# uc_board2.net
KiCad netlist of a schematic drawn in EAGLE
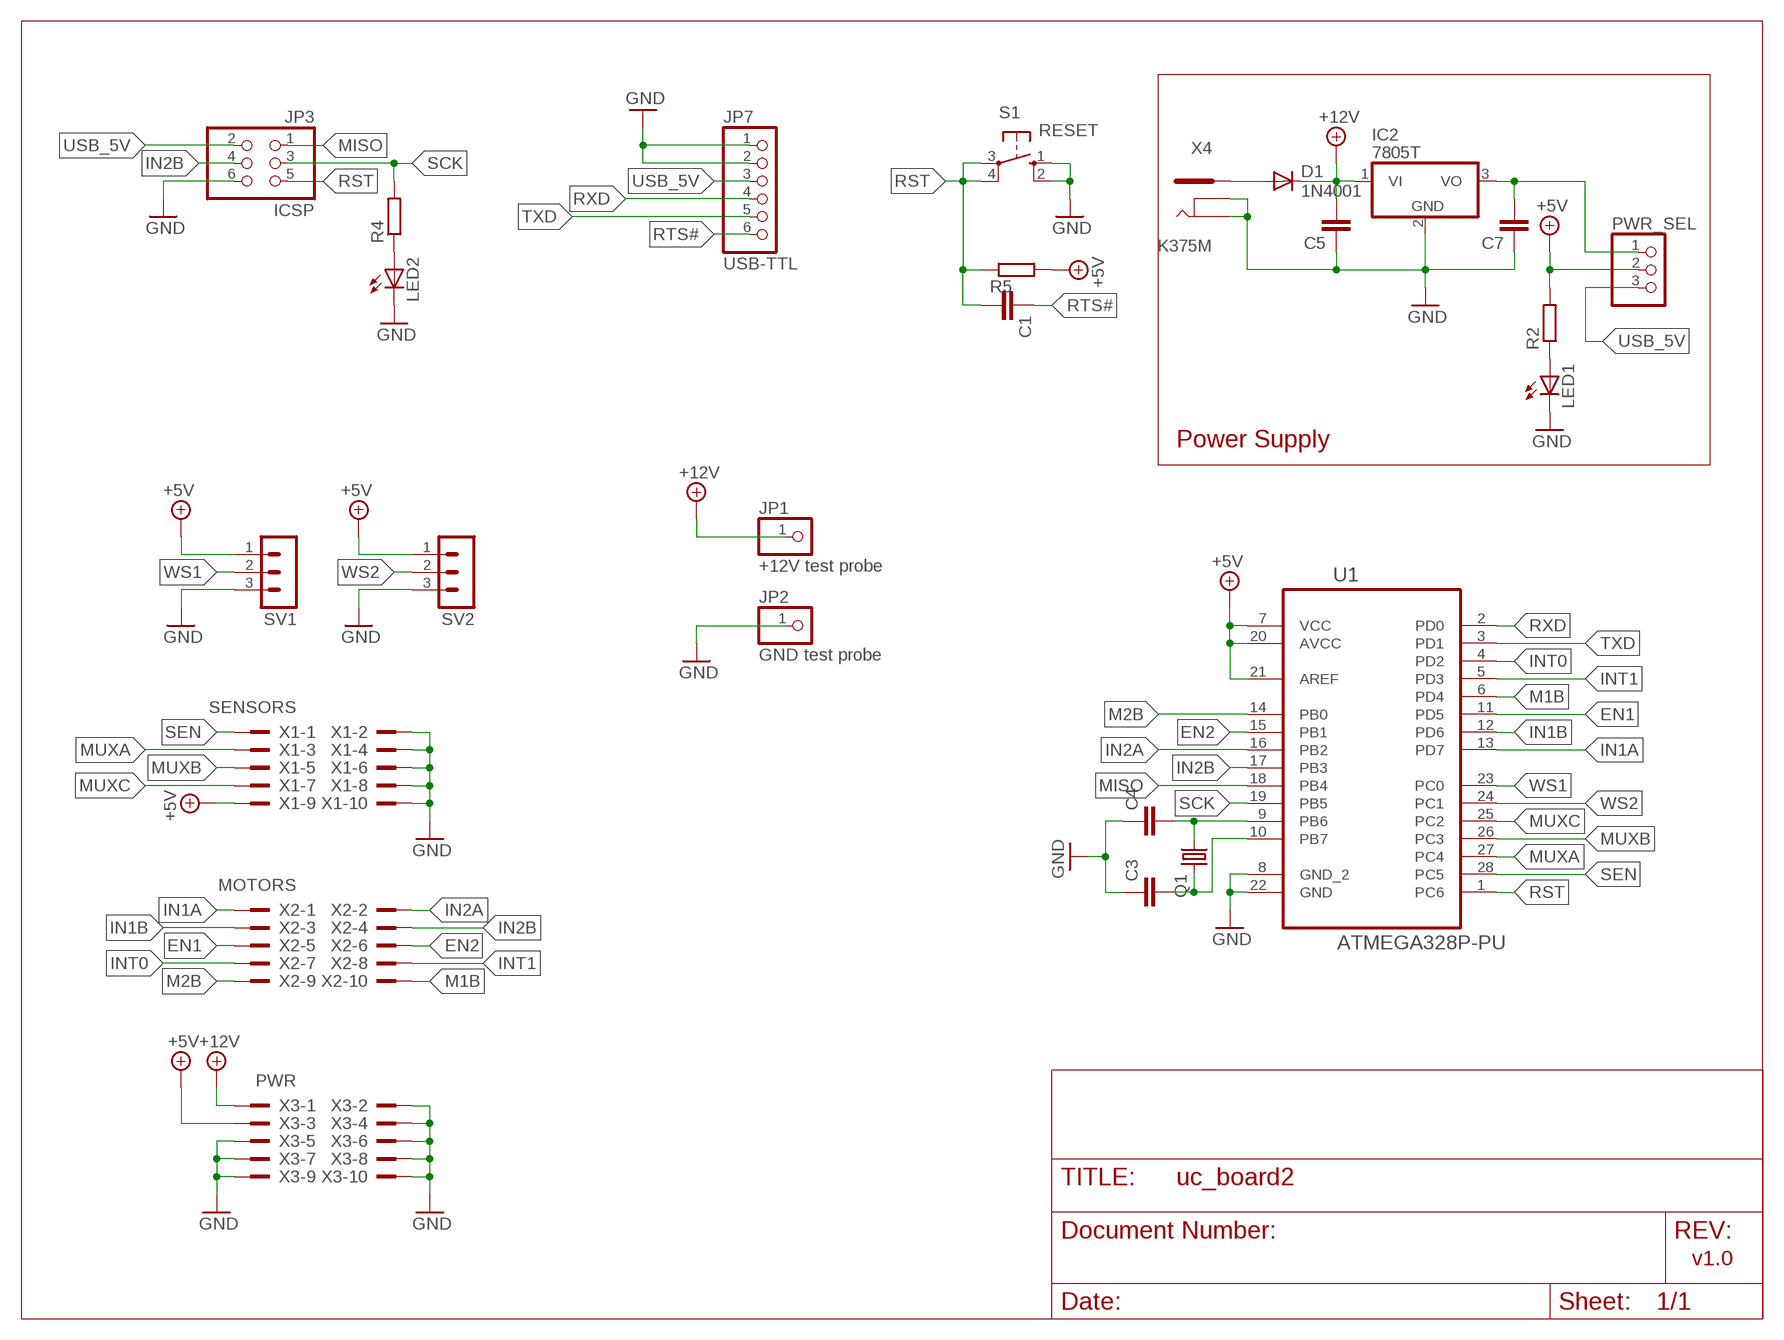
[diagram p0: schematic, sheet 1]

(export (version "E")
  (design (tool "Eeschema 10.0.6"))
  (components
    (comp (ref "C1")
      (value "C-EU050-025X075")
      (footprint "eagle-import:C050-025X075")
      (libsource (lib "eagle-import") (part "C-EU050-025X075"))
    )
    (comp (ref "C3")
      (value "C-EU025-024X044")
      (footprint "eagle-import:C025-024X044")
      (libsource (lib "eagle-import") (part "C-EU025-024X044"))
    )
    (comp (ref "C4")
      (value "C-EU025-024X044")
      (footprint "eagle-import:C025-024X044")
      (libsource (lib "eagle-import") (part "C-EU025-024X044"))
    )
    (comp (ref "C5")
      (value "C-EU025-050X050")
      (footprint "eagle-import:C025-050X050")
      (libsource (lib "eagle-import") (part "C-EU025-050X050"))
    )
    (comp (ref "C7")
      (value "C-EU025-050X050")
      (footprint "eagle-import:C025-050X050")
      (libsource (lib "eagle-import") (part "C-EU025-050X050"))
    )
    (comp (ref "D1")
      (value "1N4001")
      (footprint "eagle-import:DO41-10")
      (libsource (lib "eagle-import") (part "1N4004"))
    )
    (comp (ref "IC2")
      (value "7805T")
      (footprint "eagle-import:TO220H")
      (libsource (lib "eagle-import") (part "78T05"))
    )
    (comp (ref "JP1")
      (value "+12V test probe")
      (footprint "eagle-import:1X01")
      (libsource (lib "eagle-import") (part "PINHD-1X1"))
    )
    (comp (ref "JP2")
      (value "GND test probe")
      (footprint "eagle-import:1X01")
      (libsource (lib "eagle-import") (part "PINHD-1X1"))
    )
    (comp (ref "JP3")
      (value "ICSP")
      (footprint "eagle-import:2X03")
      (libsource (lib "eagle-import") (part "PINHD-2X3"))
    )
    (comp (ref "JP7")
      (value "USB-TTL")
      (footprint "eagle-import:1X06_90")
      (libsource (lib "eagle-import") (part "PINHD-1X6/90"))
    )
    (comp (ref "LED1")
      (value "LED5MM")
      (footprint "eagle-import:LED5MM")
      (libsource (lib "eagle-import") (part "LED5MM"))
    )
    (comp (ref "LED2")
      (value "LED5MM")
      (footprint "eagle-import:LED5MM")
      (libsource (lib "eagle-import") (part "LED5MM"))
    )
    (comp (ref "PWR_SEL")
      (value "PINHD-1X3")
      (footprint "eagle-import:1X03")
      (libsource (lib "eagle-import") (part "PINHD-1X3"))
    )
    (comp (ref "Q1")
      (value "CRYSTALHC49S")
      (footprint "eagle-import:HC49_S")
      (libsource (lib "eagle-import") (part "CRYSTALHC49S"))
    )
    (comp (ref "R2")
      (value "R-EU_0204/7")
      (footprint "eagle-import:0204_7")
      (libsource (lib "eagle-import") (part "R-EU_0204/7"))
    )
    (comp (ref "R4")
      (value "R-EU_0204/7")
      (footprint "eagle-import:0204_7")
      (libsource (lib "eagle-import") (part "R-EU_0204/7"))
    )
    (comp (ref "R5")
      (value "R-EU_0204/7")
      (footprint "eagle-import:0204_7")
      (libsource (lib "eagle-import") (part "R-EU_0204/7"))
    )
    (comp (ref "S1")
      (value "RESET")
      (footprint "eagle-import:B3F-10XX")
      (fields (field (name "MPN") "B3F-1000"))
      (libsource (lib "eagle-import") (part "10-XX"))
    )
    (comp (ref "SV1")
      (value "MA03-1")
      (footprint "eagle-import:MA03-1")
      (libsource (lib "eagle-import") (part "MA03-1"))
    )
    (comp (ref "SV2")
      (value "MA03-1")
      (footprint "eagle-import:MA03-1")
      (libsource (lib "eagle-import") (part "MA03-1"))
    )
    (comp (ref "U1")
      (value "ATMEGA328P-PU")
      (footprint "eagle-import:DIP254P762X457-28")
      (libsource (lib "eagle-import") (part "ATMEGA328P-PU"))
    )
    (comp (ref "X1")
      (value "SENSORS")
      (footprint "eagle-import:PAK100_2500-10")
      (fields (field (name "MF") "3M") (field (name "MPN") "2510-6002UB"))
      (libsource (lib "eagle-import") (part "2510-"))
    )
    (comp (ref "X2")
      (value "MOTORS")
      (footprint "eagle-import:PAK100_2500-10")
      (fields (field (name "MF") "3M") (field (name "MPN") "2510-6002UB"))
      (libsource (lib "eagle-import") (part "2510-"))
    )
    (comp (ref "X3")
      (value "PWR")
      (footprint "eagle-import:PAK100_2500-10")
      (fields (field (name "MF") "3M") (field (name "MPN") "2510-6002UB"))
      (libsource (lib "eagle-import") (part "2510-"))
    )
    (comp (ref "X4")
      (value "K375M")
      (footprint "eagle-import:K375M")
      (libsource (lib "eagle-import") (part "K375M"))
    )
  )
  (nets
    (net (code "1") (name "+5V") (class "Default")
      (node (ref "PWR_SEL") (pin "2") (pinfunction "2_2") (pintype "passive"))
      (node (ref "R2") (pin "2") (pinfunction "2_2") (pintype "passive"))
      (node (ref "R5") (pin "2") (pinfunction "2_2") (pintype "passive"))
      (node (ref "SV1") (pin "1") (pinfunction "1_1") (pintype "passive"))
      (node (ref "SV2") (pin "1") (pinfunction "1_1") (pintype "passive"))
      (node (ref "U1") (pin "20") (pinfunction "AVCC_20") (pintype "power_in"))
      (node (ref "U1") (pin "21") (pinfunction "AREF_21") (pintype "input"))
      (node (ref "U1") (pin "7") (pinfunction "VCC_7") (pintype "power_in"))
      (node (ref "X1") (pin "9") (pinfunction "KL_9") (pintype "passive"))
      (node (ref "X3") (pin "3") (pinfunction "KL_3") (pintype "passive"))
    )
    (net (code "2") (name "+12V") (class "Default")
      (node (ref "C5") (pin "2") (pinfunction "2_2") (pintype "passive"))
      (node (ref "D1") (pin "C") (pinfunction "C_C") (pintype "passive"))
      (node (ref "IC2") (pin "1") (pinfunction "VI_1") (pintype "input"))
      (node (ref "JP1") (pin "1") (pinfunction "1_1") (pintype "passive"))
      (node (ref "X3") (pin "1") (pinfunction "KL_1") (pintype "passive"))
    )
    (net (code "3") (name "EN1") (class "Default")
      (node (ref "U1") (pin "11") (pinfunction "PD5_11") (pintype "bidirectional"))
      (node (ref "X2") (pin "5") (pinfunction "KL_5") (pintype "passive"))
    )
    (net (code "4") (name "EN2") (class "Default")
      (node (ref "U1") (pin "15") (pinfunction "PB1_15") (pintype "bidirectional"))
      (node (ref "X2") (pin "6") (pinfunction "KL_6") (pintype "passive"))
    )
    (net (code "5") (name "GND") (class "Default")
      (node (ref "C3") (pin "1") (pinfunction "1_1") (pintype "passive"))
      (node (ref "C4") (pin "1") (pinfunction "1_1") (pintype "passive"))
      (node (ref "C5") (pin "1") (pinfunction "1_1") (pintype "passive"))
      (node (ref "C7") (pin "1") (pinfunction "1_1") (pintype "passive"))
      (node (ref "IC2") (pin "2") (pinfunction "GND_2") (pintype "passive"))
      (node (ref "JP2") (pin "1") (pinfunction "1_1") (pintype "passive"))
      (node (ref "JP3") (pin "6") (pinfunction "6_6") (pintype "passive"))
      (node (ref "JP7") (pin "1") (pinfunction "1_1") (pintype "passive"))
      (node (ref "JP7") (pin "2") (pinfunction "2_2") (pintype "passive"))
      (node (ref "LED1") (pin "K") (pinfunction "C_K") (pintype "passive"))
      (node (ref "LED2") (pin "K") (pinfunction "C_K") (pintype "passive"))
      (node (ref "S1") (pin "1") (pinfunction "S_1") (pintype "passive"))
      (node (ref "S1") (pin "2") (pinfunction "S1_2") (pintype "passive"))
      (node (ref "SV1") (pin "3") (pinfunction "3_3") (pintype "passive"))
      (node (ref "SV2") (pin "3") (pinfunction "3_3") (pintype "passive"))
      (node (ref "U1") (pin "22") (pinfunction "GND_22") (pintype "passive"))
      (node (ref "U1") (pin "8") (pinfunction "GND_2_8") (pintype "passive"))
      (node (ref "X1") (pin "10") (pinfunction "KL_10") (pintype "passive"))
      (node (ref "X1") (pin "2") (pinfunction "KL_2") (pintype "passive"))
      (node (ref "X1") (pin "4") (pinfunction "KL_4") (pintype "passive"))
      (node (ref "X1") (pin "6") (pinfunction "KL_6") (pintype "passive"))
      (node (ref "X1") (pin "8") (pinfunction "KL_8") (pintype "passive"))
      (node (ref "X3") (pin "10") (pinfunction "KL_10") (pintype "passive"))
      (node (ref "X3") (pin "2") (pinfunction "KL_2") (pintype "passive"))
      (node (ref "X3") (pin "4") (pinfunction "KL_4") (pintype "passive"))
      (node (ref "X3") (pin "5") (pinfunction "KL_5") (pintype "passive"))
      (node (ref "X3") (pin "6") (pinfunction "KL_6") (pintype "passive"))
      (node (ref "X3") (pin "7") (pinfunction "KL_7") (pintype "passive"))
      (node (ref "X3") (pin "8") (pinfunction "KL_8") (pintype "passive"))
      (node (ref "X3") (pin "9") (pinfunction "KL_9") (pintype "passive"))
      (node (ref "X4") (pin "2") (pinfunction "2_2") (pintype "passive"))
      (node (ref "X4") (pin "3") (pinfunction "3_3") (pintype "passive"))
    )
    (net (code "6") (name "IN1A") (class "Default")
      (node (ref "U1") (pin "13") (pinfunction "PD7_13") (pintype "bidirectional"))
      (node (ref "X2") (pin "1") (pinfunction "KL_1") (pintype "passive"))
    )
    (net (code "7") (name "IN1B") (class "Default")
      (node (ref "U1") (pin "12") (pinfunction "PD6_12") (pintype "bidirectional"))
      (node (ref "X2") (pin "3") (pinfunction "KL_3") (pintype "passive"))
    )
    (net (code "8") (name "IN2A") (class "Default")
      (node (ref "U1") (pin "16") (pinfunction "PB2_16") (pintype "bidirectional"))
      (node (ref "X2") (pin "2") (pinfunction "KL_2") (pintype "passive"))
    )
    (net (code "9") (name "IN2B") (class "Default")
      (node (ref "JP3") (pin "4") (pinfunction "4_4") (pintype "passive"))
      (node (ref "U1") (pin "17") (pinfunction "PB3_17") (pintype "bidirectional"))
      (node (ref "X2") (pin "4") (pinfunction "KL_4") (pintype "passive"))
    )
    (net (code "10") (name "INT0") (class "Default")
      (node (ref "U1") (pin "4") (pinfunction "PD2_4") (pintype "bidirectional"))
      (node (ref "X2") (pin "7") (pinfunction "KL_7") (pintype "passive"))
    )
    (net (code "11") (name "INT1") (class "Default")
      (node (ref "U1") (pin "5") (pinfunction "PD3_5") (pintype "bidirectional"))
      (node (ref "X2") (pin "8") (pinfunction "KL_8") (pintype "passive"))
    )
    (net (code "12") (name "M1B") (class "Default")
      (node (ref "U1") (pin "6") (pinfunction "PD4_6") (pintype "bidirectional"))
      (node (ref "X2") (pin "10") (pinfunction "KL_10") (pintype "passive"))
    )
    (net (code "13") (name "M2B") (class "Default")
      (node (ref "U1") (pin "14") (pinfunction "PB0_14") (pintype "bidirectional"))
      (node (ref "X2") (pin "9") (pinfunction "KL_9") (pintype "passive"))
    )
    (net (code "14") (name "MISO") (class "Default")
      (node (ref "JP3") (pin "1") (pinfunction "1_1") (pintype "passive"))
      (node (ref "U1") (pin "18") (pinfunction "PB4_18") (pintype "bidirectional"))
    )
    (net (code "15") (name "MUXA") (class "Default")
      (node (ref "U1") (pin "27") (pinfunction "PC4_27") (pintype "bidirectional"))
      (node (ref "X1") (pin "3") (pinfunction "KL_3") (pintype "passive"))
    )
    (net (code "16") (name "MUXB") (class "Default")
      (node (ref "U1") (pin "26") (pinfunction "PC3_26") (pintype "bidirectional"))
      (node (ref "X1") (pin "5") (pinfunction "KL_5") (pintype "passive"))
    )
    (net (code "17") (name "MUXC") (class "Default")
      (node (ref "U1") (pin "25") (pinfunction "PC2_25") (pintype "bidirectional"))
      (node (ref "X1") (pin "7") (pinfunction "KL_7") (pintype "passive"))
    )
    (net (code "18") (name "Net-(D1-PadA)") (class "Default")
      (node (ref "D1") (pin "A") (pinfunction "A_A") (pintype "passive"))
      (node (ref "X4") (pin "1") (pinfunction "1_1") (pintype "passive"))
    )
    (net (code "19") (name "Net-(IC2-VO)") (class "Default")
      (node (ref "C7") (pin "2") (pinfunction "2_2") (pintype "passive"))
      (node (ref "IC2") (pin "3") (pinfunction "VO_3") (pintype "passive"))
      (node (ref "PWR_SEL") (pin "1") (pinfunction "1_1") (pintype "passive"))
    )
    (net (code "20") (name "Net-(LED1-PadA)") (class "Default")
      (node (ref "LED1") (pin "A") (pinfunction "A_A") (pintype "passive"))
      (node (ref "R2") (pin "1") (pinfunction "1_1") (pintype "passive"))
    )
    (net (code "21") (name "Net-(LED2-PadA)") (class "Default")
      (node (ref "LED2") (pin "A") (pinfunction "A_A") (pintype "passive"))
      (node (ref "R4") (pin "1") (pinfunction "1_1") (pintype "passive"))
    )
    (net (code "22") (name "Net-(U1-PB6)") (class "Default")
      (node (ref "C4") (pin "2") (pinfunction "2_2") (pintype "passive"))
      (node (ref "Q1") (pin "1") (pinfunction "1_1") (pintype "passive"))
      (node (ref "U1") (pin "9") (pinfunction "PB6_9") (pintype "bidirectional"))
    )
    (net (code "23") (name "Net-(U1-PB7)") (class "Default")
      (node (ref "C3") (pin "2") (pinfunction "2_2") (pintype "passive"))
      (node (ref "Q1") (pin "2") (pinfunction "2_2") (pintype "passive"))
      (node (ref "U1") (pin "10") (pinfunction "PB7_10") (pintype "bidirectional"))
    )
    (net (code "24") (name "RST") (class "Default")
      (node (ref "C1") (pin "2") (pinfunction "2_2") (pintype "passive"))
      (node (ref "JP3") (pin "5") (pinfunction "5_5") (pintype "passive"))
      (node (ref "R5") (pin "1") (pinfunction "1_1") (pintype "passive"))
      (node (ref "S1") (pin "3") (pinfunction "P_3") (pintype "passive"))
      (node (ref "S1") (pin "4") (pinfunction "P1_4") (pintype "passive"))
      (node (ref "U1") (pin "1") (pinfunction "PC6_1") (pintype "bidirectional"))
    )
    (net (code "25") (name "RTS#") (class "Default")
      (node (ref "C1") (pin "1") (pinfunction "1_1") (pintype "passive"))
      (node (ref "JP7") (pin "6") (pinfunction "6_6") (pintype "passive"))
    )
    (net (code "26") (name "RXD") (class "Default")
      (node (ref "JP7") (pin "4") (pinfunction "4_4") (pintype "passive"))
      (node (ref "U1") (pin "2") (pinfunction "PD0_2") (pintype "bidirectional"))
    )
    (net (code "27") (name "SCK") (class "Default")
      (node (ref "JP3") (pin "3") (pinfunction "3_3") (pintype "passive"))
      (node (ref "R4") (pin "2") (pinfunction "2_2") (pintype "passive"))
      (node (ref "U1") (pin "19") (pinfunction "PB5_19") (pintype "bidirectional"))
    )
    (net (code "28") (name "SEN") (class "Default")
      (node (ref "U1") (pin "28") (pinfunction "PC5_28") (pintype "bidirectional"))
      (node (ref "X1") (pin "1") (pinfunction "KL_1") (pintype "passive"))
    )
    (net (code "29") (name "TXD") (class "Default")
      (node (ref "JP7") (pin "5") (pinfunction "5_5") (pintype "passive"))
      (node (ref "U1") (pin "3") (pinfunction "PD1_3") (pintype "bidirectional"))
    )
    (net (code "30") (name "USB_5V") (class "Default")
      (node (ref "JP3") (pin "2") (pinfunction "2_2") (pintype "passive"))
      (node (ref "JP7") (pin "3") (pinfunction "3_3") (pintype "passive"))
      (node (ref "PWR_SEL") (pin "3") (pinfunction "3_3") (pintype "passive"))
    )
    (net (code "31") (name "WS1") (class "Default")
      (node (ref "SV1") (pin "2") (pinfunction "2_2") (pintype "passive"))
      (node (ref "U1") (pin "23") (pinfunction "PC0_23") (pintype "bidirectional"))
    )
    (net (code "32") (name "WS2") (class "Default")
      (node (ref "SV2") (pin "2") (pinfunction "2_2") (pintype "passive"))
      (node (ref "U1") (pin "24") (pinfunction "PC1_24") (pintype "bidirectional"))
    )
  )
)
